# roller-shutter.net
KiCad netlist of a schematic drawn in EAGLE
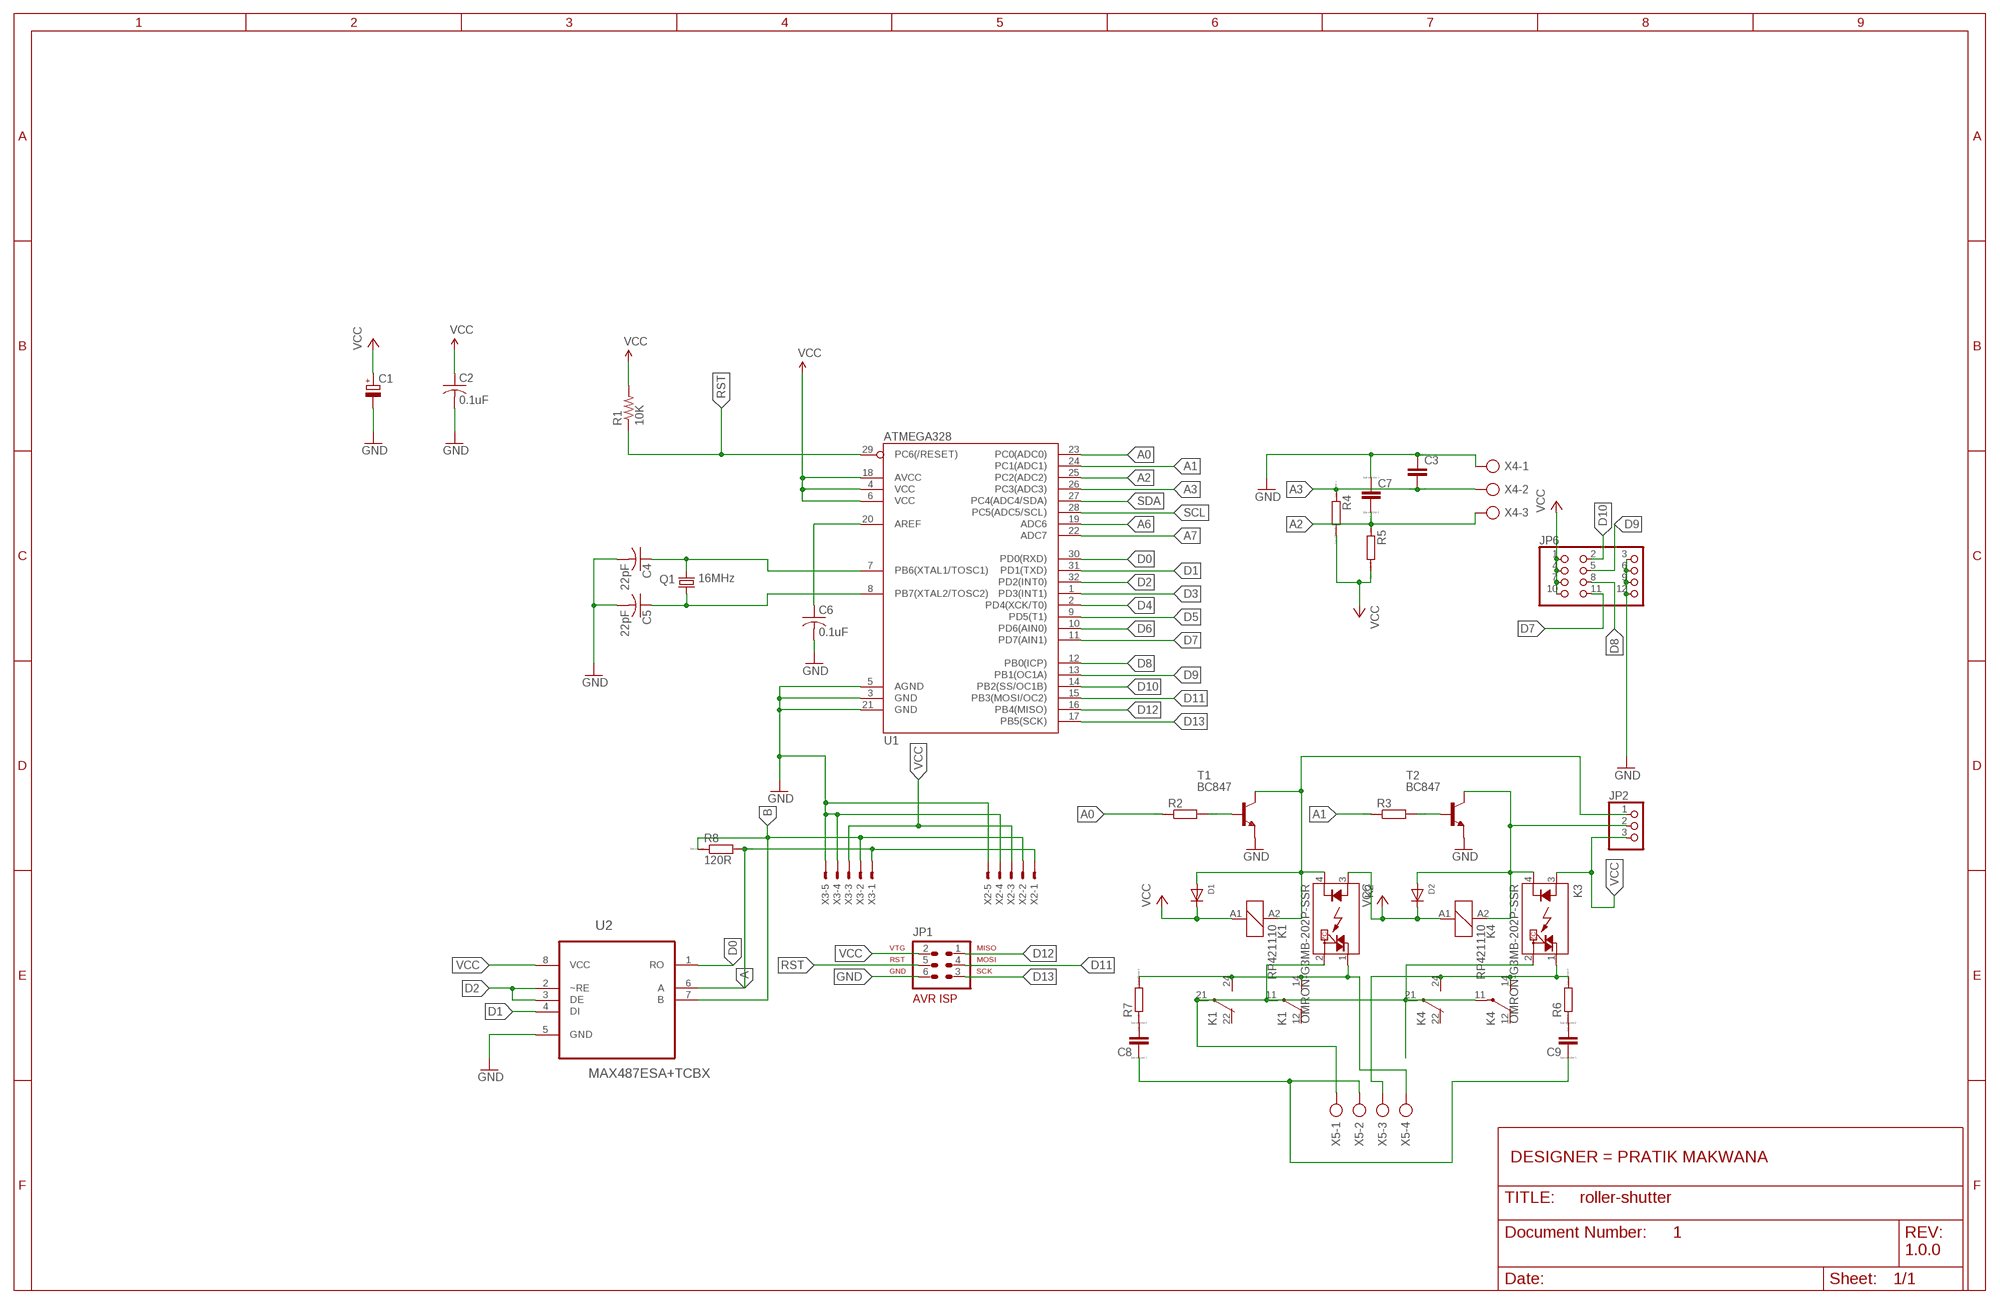
[diagram p0: schematic, sheet 1]

(export (version "E")
  (design (tool "Eeschema 10.0.6"))
  (components
    (comp (ref "C1")
      (value "CPOL-EUSANYO_SMD_C6")
      (footprint "eagle-import:SANYO-OSCON_SMD_C6")
      (libsource (lib "eagle-import") (part "CPOL-EUSANYO_SMD_C6"))
    )
    (comp (ref "C2")
      (value "0.1uF")
      (footprint "eagle-import:C0805")
      (libsource (lib "eagle-import") (part "C-USC0805"))
    )
    (comp (ref "C3") (value "C") (footprint "eagle-import:C0805") (libsource (lib "eagle-import") (part "C")))
    (comp (ref "C4")
      (value "22pF")
      (footprint "eagle-import:C1206")
      (libsource (lib "eagle-import") (part "C-USC1206"))
    )
    (comp (ref "C5")
      (value "22pF")
      (footprint "eagle-import:C1206")
      (libsource (lib "eagle-import") (part "C-USC1206"))
    )
    (comp (ref "C6")
      (value "0.1uF")
      (footprint "eagle-import:C0805")
      (libsource (lib "eagle-import") (part "C-USC0805"))
    )
    (comp (ref "C7") (value "C") (footprint "eagle-import:C0805") (libsource (lib "eagle-import") (part "C")))
    (comp (ref "C8")
      (value "CC1812")
      (footprint "eagle-import:C1812")
      (libsource (lib "eagle-import") (part "CC1812"))
    )
    (comp (ref "C9")
      (value "CC1812")
      (footprint "eagle-import:C1812")
      (libsource (lib "eagle-import") (part "CC1812"))
    )
    (comp (ref "D1")
      (value "DIODE_SOD-123FL")
      (footprint "eagle-import:SOD-123FL")
      (libsource (lib "eagle-import") (part "DIODE_SOD-123FL"))
    )
    (comp (ref "D2")
      (value "DIODE_SOD-123FL")
      (footprint "eagle-import:SOD-123FL")
      (libsource (lib "eagle-import") (part "DIODE_SOD-123FL"))
    )
    (comp (ref "JP1")
      (value "AVR-ISP-6")
      (footprint "eagle-import:AVR-ISP-6")
      (libsource (lib "eagle-import") (part "AVR-ISP-6"))
    )
    (comp (ref "JP2")
      (value "PINHD-1X3")
      (footprint "eagle-import:1X03")
      (libsource (lib "eagle-import") (part "PINHD-1X3"))
    )
    (comp (ref "JP6")
      (value "PINHD-3X4")
      (footprint "eagle-import:3X04")
      (libsource (lib "eagle-import") (part "PINHD-3X4"))
    )
    (comp (ref "K1")
      (value "RP421110")
      (footprint "eagle-import:RP420")
      (fields (field (name "MF") "TYCO ELECTRONICS"))
      (libsource (lib "eagle-import") (part "RP42?1110"))
    )
    (comp (ref "K2")
      (value "OMRON-G3MB-202P-SSR")
      (footprint "eagle-import:OMRON-G3MB-202P-SSR")
      (libsource (lib "eagle-import") (part "OMRON-G3MB-202P-SSR"))
    )
    (comp (ref "K3")
      (value "OMRON-G3MB-202P-SSR")
      (footprint "eagle-import:OMRON-G3MB-202P-SSR")
      (libsource (lib "eagle-import") (part "OMRON-G3MB-202P-SSR"))
    )
    (comp (ref "K4")
      (value "RP421110")
      (footprint "eagle-import:RP420")
      (fields (field (name "MF") "TYCO ELECTRONICS"))
      (libsource (lib "eagle-import") (part "RP42?1110"))
    )
    (comp (ref "Q1")
      (value "16MHz")
      (footprint "eagle-import:HC49_S")
      (libsource (lib "eagle-import") (part "CRYTALHC49S"))
    )
    (comp (ref "R1")
      (value "10K")
      (footprint "eagle-import:R1206")
      (libsource (lib "eagle-import") (part "R-US_R1206"))
    )
    (comp (ref "R2")
      (value "RR1206")
      (footprint "eagle-import:R1206")
      (libsource (lib "eagle-import") (part "RR1206"))
    )
    (comp (ref "R3")
      (value "RR1206")
      (footprint "eagle-import:R1206")
      (libsource (lib "eagle-import") (part "RR1206"))
    )
    (comp (ref "R4")
      (value "RR1206")
      (footprint "eagle-import:R1206")
      (libsource (lib "eagle-import") (part "RR1206"))
    )
    (comp (ref "R5")
      (value "RR1206")
      (footprint "eagle-import:R1206")
      (libsource (lib "eagle-import") (part "RR1206"))
    )
    (comp (ref "R6")
      (value "RR2512")
      (footprint "eagle-import:R2512")
      (libsource (lib "eagle-import") (part "RR2512"))
    )
    (comp (ref "R7")
      (value "RR2512")
      (footprint "eagle-import:R2512")
      (libsource (lib "eagle-import") (part "RR2512"))
    )
    (comp (ref "R8")
      (value "120R")
      (footprint "eagle-import:R0603")
      (libsource (lib "eagle-import") (part "RR0603"))
    )
    (comp (ref "T1")
      (value "BC847")
      (footprint "eagle-import:SOT23")
      (libsource (lib "eagle-import") (part "BC847"))
    )
    (comp (ref "T2")
      (value "BC847")
      (footprint "eagle-import:SOT23")
      (libsource (lib "eagle-import") (part "BC847"))
    )
    (comp (ref "U1")
      (value "ATMEGA328")
      (footprint "eagle-import:TQFP32-08")
      (libsource (lib "eagle-import") (part "ATMEGA328"))
    )
    (comp (ref "U2")
      (value "MAX487ESA+TCBX")
      (footprint "eagle-import:SOIC127P600X175-8N")
      (fields (field (name "MF") "Maxim Integrated"))
      (libsource (lib "eagle-import") (part "MAX487ESA+TCBX"))
    )
    (comp (ref "X2")
      (value "JST-XH-05-PIN-LONG-PAD")
      (footprint "eagle-import:JST-XH-05-PACKAGE-LONG-PAD")
      (libsource (lib "eagle-import") (part "JST-XH-05-PIN-LONG-PAD"))
    )
    (comp (ref "X3")
      (value "JST-XH-05-PIN-LONG-PAD")
      (footprint "eagle-import:JST-XH-05-PACKAGE-LONG-PAD")
      (libsource (lib "eagle-import") (part "JST-XH-05-PIN-LONG-PAD"))
    )
    (comp (ref "X4")
      (value "AK500/3")
      (footprint "eagle-import:AK500_3")
      (libsource (lib "eagle-import") (part "AK500/3"))
    )
    (comp (ref "X5")
      (value "AK500/4")
      (footprint "eagle-import:AK500_4")
      (libsource (lib "eagle-import") (part "AK500/4"))
    )
  )
  (nets
    (net (code "1") (name "A") (class "Default")
      (node (ref "R8") (pin "2") (pinfunction "2_2") (pintype "passive"))
      (node (ref "U2") (pin "6") (pinfunction "A_6") (pintype "bidirectional"))
      (node (ref "X2") (pin "1") (pinfunction "S_1") (pintype "passive"))
      (node (ref "X3") (pin "1") (pinfunction "S_1") (pintype "passive"))
    )
    (net (code "2") (name "A0") (class "Default")
      (node (ref "R2") (pin "1") (pinfunction "1_1") (pintype "passive"))
      (node (ref "U1") (pin "23") (pinfunction "PC0(ADC0)_23") (pintype "bidirectional"))
    )
    (net (code "3") (name "A1") (class "Default")
      (node (ref "R3") (pin "1") (pinfunction "1_1") (pintype "passive"))
      (node (ref "U1") (pin "24") (pinfunction "PC1(ADC1)_24") (pintype "bidirectional"))
    )
    (net (code "4") (name "A2") (class "Default")
      (node (ref "C7") (pin "2") (pinfunction "2_2") (pintype "passive"))
      (node (ref "R5") (pin "1") (pinfunction "1_1") (pintype "passive"))
      (node (ref "U1") (pin "25") (pinfunction "PC2(ADC2)_25") (pintype "bidirectional"))
      (node (ref "X4") (pin "3") (pinfunction "KL_3") (pintype "passive"))
    )
    (net (code "5") (name "A3") (class "Default")
      (node (ref "C3") (pin "2") (pinfunction "2_2") (pintype "passive"))
      (node (ref "R4") (pin "1") (pinfunction "1_1") (pintype "passive"))
      (node (ref "U1") (pin "26") (pinfunction "PC3(ADC3)_26") (pintype "bidirectional"))
      (node (ref "X4") (pin "2") (pinfunction "KL_2") (pintype "passive"))
    )
    (net (code "6") (name "A6") (class "Default")
      (node (ref "U1") (pin "19") (pinfunction "ADC6_19") (pintype "bidirectional"))
    )
    (net (code "7") (name "A7") (class "Default")
      (node (ref "U1") (pin "22") (pinfunction "ADC7_22") (pintype "bidirectional"))
    )
    (net (code "8") (name "B") (class "Default")
      (node (ref "R8") (pin "1") (pinfunction "1_1") (pintype "passive"))
      (node (ref "U2") (pin "7") (pinfunction "B_7") (pintype "bidirectional"))
      (node (ref "X2") (pin "2") (pinfunction "S_2") (pintype "passive"))
      (node (ref "X3") (pin "2") (pinfunction "S_2") (pintype "passive"))
    )
    (net (code "9") (name "D0") (class "Default")
      (node (ref "U1") (pin "30") (pinfunction "PD0(RXD)_30") (pintype "bidirectional"))
      (node (ref "U2") (pin "1") (pinfunction "RO_1") (pintype "output"))
    )
    (net (code "10") (name "D1") (class "Default")
      (node (ref "U1") (pin "31") (pinfunction "PD1(TXD)_31") (pintype "bidirectional"))
      (node (ref "U2") (pin "4") (pinfunction "DI_4") (pintype "input"))
    )
    (net (code "11") (name "D2") (class "Default")
      (node (ref "U1") (pin "32") (pinfunction "PD2(INT0)_32") (pintype "bidirectional"))
      (node (ref "U2") (pin "2") (pinfunction "~{RE}_2") (pintype "input"))
      (node (ref "U2") (pin "3") (pinfunction "DE_3") (pintype "input"))
    )
    (net (code "12") (name "D3") (class "Default")
      (node (ref "U1") (pin "1") (pinfunction "PD3(INT1)_1") (pintype "bidirectional"))
    )
    (net (code "13") (name "D4") (class "Default")
      (node (ref "U1") (pin "2") (pinfunction "PD4(XCK/T0)_2") (pintype "bidirectional"))
    )
    (net (code "14") (name "D5") (class "Default")
      (node (ref "U1") (pin "9") (pinfunction "PD5(T1)_9") (pintype "bidirectional"))
    )
    (net (code "15") (name "D6") (class "Default")
      (node (ref "U1") (pin "10") (pinfunction "PD6(AIN0)_10") (pintype "bidirectional"))
    )
    (net (code "16") (name "D7") (class "Default")
      (node (ref "JP6") (pin "11") (pinfunction "11_11") (pintype "passive"))
      (node (ref "U1") (pin "11") (pinfunction "PD7(AIN1)_11") (pintype "bidirectional"))
    )
    (net (code "17") (name "D8") (class "Default")
      (node (ref "JP6") (pin "8") (pinfunction "8_8") (pintype "passive"))
      (node (ref "U1") (pin "12") (pinfunction "PB0(ICP)_12") (pintype "bidirectional"))
    )
    (net (code "18") (name "D9") (class "Default")
      (node (ref "JP6") (pin "5") (pinfunction "5_5") (pintype "passive"))
      (node (ref "U1") (pin "13") (pinfunction "PB1(OC1A)_13") (pintype "bidirectional"))
    )
    (net (code "19") (name "D10") (class "Default")
      (node (ref "JP6") (pin "2") (pinfunction "2_2") (pintype "passive"))
      (node (ref "U1") (pin "14") (pinfunction "PB2(SS/OC1B)_14") (pintype "bidirectional"))
    )
    (net (code "20") (name "D11") (class "Default")
      (node (ref "JP1") (pin "4") (pinfunction "4_4") (pintype "passive"))
      (node (ref "U1") (pin "15") (pinfunction "PB3(MOSI/OC2)_15") (pintype "bidirectional"))
    )
    (net (code "21") (name "D12") (class "Default")
      (node (ref "JP1") (pin "1") (pinfunction "1_1") (pintype "passive"))
      (node (ref "U1") (pin "16") (pinfunction "PB4(MISO)_16") (pintype "bidirectional"))
    )
    (net (code "22") (name "D13") (class "Default")
      (node (ref "JP1") (pin "3") (pinfunction "3_3") (pintype "passive"))
      (node (ref "U1") (pin "17") (pinfunction "PB5(SCK)_17") (pintype "bidirectional"))
    )
    (net (code "23") (name "GND") (class "Default")
      (node (ref "C1") (pin "-") (pinfunction "-_-") (pintype "passive"))
      (node (ref "C2") (pin "2") (pinfunction "2_2") (pintype "passive"))
      (node (ref "C3") (pin "1") (pinfunction "1_1") (pintype "passive"))
      (node (ref "C4") (pin "2") (pinfunction "2_2") (pintype "passive"))
      (node (ref "C5") (pin "2") (pinfunction "2_2") (pintype "passive"))
      (node (ref "C6") (pin "2") (pinfunction "2_2") (pintype "passive"))
      (node (ref "C7") (pin "1") (pinfunction "1_1") (pintype "passive"))
      (node (ref "JP1") (pin "6") (pinfunction "6_6") (pintype "passive"))
      (node (ref "JP6") (pin "12") (pinfunction "12_12") (pintype "passive"))
      (node (ref "JP6") (pin "3") (pinfunction "3_3") (pintype "passive"))
      (node (ref "JP6") (pin "6") (pinfunction "6_6") (pintype "passive"))
      (node (ref "JP6") (pin "9") (pinfunction "9_9") (pintype "passive"))
      (node (ref "T1") (pin "2") (pinfunction "E_2") (pintype "passive"))
      (node (ref "T2") (pin "2") (pinfunction "E_2") (pintype "passive"))
      (node (ref "U1") (pin "21") (pinfunction "GND_21") (pintype "bidirectional"))
      (node (ref "U1") (pin "3") (pinfunction "GND_3") (pintype "bidirectional"))
      (node (ref "U1") (pin "5") (pinfunction "AGND_5") (pintype "bidirectional"))
      (node (ref "U2") (pin "5") (pinfunction "GND_5") (pintype "passive"))
      (node (ref "X2") (pin "4") (pinfunction "S_4") (pintype "passive"))
      (node (ref "X2") (pin "5") (pinfunction "S_5") (pintype "passive"))
      (node (ref "X3") (pin "4") (pinfunction "S_4") (pintype "passive"))
      (node (ref "X3") (pin "5") (pinfunction "S_5") (pintype "passive"))
      (node (ref "X4") (pin "1") (pinfunction "KL_1") (pintype "passive"))
    )
    (net (code "24") (name "Net-(C8-Pad2)") (class "Default")
      (node (ref "C8") (pin "2") (pinfunction "2_2") (pintype "passive"))
      (node (ref "R7") (pin "1") (pinfunction "1_1") (pintype "passive"))
    )
    (net (code "25") (name "Net-(C9-Pad2)") (class "Default")
      (node (ref "C9") (pin "2") (pinfunction "2_2") (pintype "passive"))
      (node (ref "R6") (pin "1") (pinfunction "1_1") (pintype "passive"))
    )
    (net (code "26") (name "Net-(K1A-1)") (class "Default")
      (node (ref "D1") (pin "A") (pinfunction "A_A") (pintype "passive"))
      (node (ref "JP2") (pin "1") (pinfunction "1_1") (pintype "passive"))
      (node (ref "K1") (pin "A2") (pinfunction "1_A2") (pintype "passive"))
      (node (ref "K2") (pin "4") (pinfunction "K_4") (pintype "passive"))
      (node (ref "T1") (pin "3") (pinfunction "C_3") (pintype "passive"))
    )
    (net (code "27") (name "Net-(K1B-P)") (class "Default")
      (node (ref "K1") (pin "11") (pinfunction "P_11") (pintype "passive"))
      (node (ref "K1") (pin "21") (pinfunction "P_21") (pintype "passive"))
      (node (ref "K2") (pin "2") (pinfunction "DS2_2") (pintype "passive"))
      (node (ref "K3") (pin "2") (pinfunction "DS2_2") (pintype "passive"))
      (node (ref "K4") (pin "11") (pinfunction "P_11") (pintype "passive"))
      (node (ref "K4") (pin "21") (pinfunction "P_21") (pintype "passive"))
      (node (ref "X5") (pin "1") (pinfunction "KL_1") (pintype "passive"))
    )
    (net (code "28") (name "Net-(K1B-S)") (class "Default")
      (node (ref "K1") (pin "14") (pinfunction "S_14") (pintype "passive"))
      (node (ref "K1") (pin "24") (pinfunction "S_24") (pintype "passive"))
      (node (ref "K2") (pin "1") (pinfunction "DS1_1") (pintype "passive"))
      (node (ref "R7") (pin "2") (pinfunction "2_2") (pintype "passive"))
      (node (ref "X5") (pin "4") (pinfunction "KL_4") (pintype "passive"))
    )
    (net (code "29") (name "Net-(K3-DS1)") (class "Default")
      (node (ref "K3") (pin "1") (pinfunction "DS1_1") (pintype "passive"))
      (node (ref "K4") (pin "14") (pinfunction "S_14") (pintype "passive"))
      (node (ref "K4") (pin "24") (pinfunction "S_24") (pintype "passive"))
      (node (ref "R6") (pin "2") (pinfunction "2_2") (pintype "passive"))
      (node (ref "X5") (pin "3") (pinfunction "KL_3") (pintype "passive"))
    )
    (net (code "30") (name "Net-(K3-K)") (class "Default")
      (node (ref "D2") (pin "A") (pinfunction "A_A") (pintype "passive"))
      (node (ref "JP2") (pin "2") (pinfunction "2_2") (pintype "passive"))
      (node (ref "K3") (pin "4") (pinfunction "K_4") (pintype "passive"))
      (node (ref "K4") (pin "A2") (pinfunction "1_A2") (pintype "passive"))
      (node (ref "T2") (pin "3") (pinfunction "C_3") (pintype "passive"))
    )
    (net (code "31") (name "Net-(T1-B)") (class "Default")
      (node (ref "R2") (pin "2") (pinfunction "2_2") (pintype "passive"))
      (node (ref "T1") (pin "1") (pinfunction "B_1") (pintype "passive"))
    )
    (net (code "32") (name "Net-(T2-B)") (class "Default")
      (node (ref "R3") (pin "2") (pinfunction "2_2") (pintype "passive"))
      (node (ref "T2") (pin "1") (pinfunction "B_1") (pintype "passive"))
    )
    (net (code "33") (name "Net-(U1-AREF)") (class "Default")
      (node (ref "C6") (pin "1") (pinfunction "1_1") (pintype "passive"))
      (node (ref "U1") (pin "20") (pinfunction "AREF_20") (pintype "bidirectional"))
    )
    (net (code "34") (name "Net-(U1-PB6(XTAL1{slash}TOSC1))") (class "Default")
      (node (ref "C4") (pin "1") (pinfunction "1_1") (pintype "passive"))
      (node (ref "Q1") (pin "2") (pinfunction "2_2") (pintype "passive"))
      (node (ref "U1") (pin "7") (pinfunction "PB6(XTAL1/TOSC1)_7") (pintype "bidirectional"))
    )
    (net (code "35") (name "Net-(U1-PB7(XTAL2{slash}TOSC2))") (class "Default")
      (node (ref "C5") (pin "1") (pinfunction "1_1") (pintype "passive"))
      (node (ref "Q1") (pin "1") (pinfunction "1_1") (pintype "passive"))
      (node (ref "U1") (pin "8") (pinfunction "PB7(XTAL2/TOSC2)_8") (pintype "bidirectional"))
    )
    (net (code "36") (name "Net-(X5B-KL)") (class "Default")
      (node (ref "C8") (pin "1") (pinfunction "1_1") (pintype "passive"))
      (node (ref "C9") (pin "1") (pinfunction "1_1") (pintype "passive"))
      (node (ref "X5") (pin "2") (pinfunction "KL_2") (pintype "passive"))
    )
    (net (code "37") (name "RST") (class "Default")
      (node (ref "JP1") (pin "5") (pinfunction "5_5") (pintype "passive"))
      (node (ref "R1") (pin "1") (pinfunction "1_1") (pintype "passive"))
      (node (ref "U1") (pin "29") (pinfunction "PC6(/RESET)_29") (pintype "bidirectional"))
    )
    (net (code "38") (name "SCL") (class "Default")
      (node (ref "U1") (pin "28") (pinfunction "PC5(ADC5/SCL)_28") (pintype "bidirectional"))
    )
    (net (code "39") (name "SDA") (class "Default")
      (node (ref "U1") (pin "27") (pinfunction "PC4(ADC4/SDA)_27") (pintype "bidirectional"))
    )
    (net (code "40") (name "VCC") (class "Default")
      (node (ref "C1") (pin "+") (pinfunction "+_+") (pintype "passive"))
      (node (ref "C2") (pin "1") (pinfunction "1_1") (pintype "passive"))
      (node (ref "D1") (pin "C") (pinfunction "C_C") (pintype "passive"))
      (node (ref "D2") (pin "C") (pinfunction "C_C") (pintype "passive"))
      (node (ref "JP1") (pin "2") (pinfunction "2_2") (pintype "passive"))
      (node (ref "JP2") (pin "3") (pinfunction "3_3") (pintype "passive"))
      (node (ref "JP6") (pin "1") (pinfunction "1_1") (pintype "passive"))
      (node (ref "JP6") (pin "10") (pinfunction "10_10") (pintype "passive"))
      (node (ref "JP6") (pin "4") (pinfunction "4_4") (pintype "passive"))
      (node (ref "JP6") (pin "7") (pinfunction "7_7") (pintype "passive"))
      (node (ref "K1") (pin "A1") (pinfunction "2_A1") (pintype "passive"))
      (node (ref "K2") (pin "3") (pinfunction "A_3") (pintype "passive"))
      (node (ref "K3") (pin "3") (pinfunction "A_3") (pintype "passive"))
      (node (ref "K4") (pin "A1") (pinfunction "2_A1") (pintype "passive"))
      (node (ref "R1") (pin "2") (pinfunction "2_2") (pintype "passive"))
      (node (ref "R4") (pin "2") (pinfunction "2_2") (pintype "passive"))
      (node (ref "R5") (pin "2") (pinfunction "2_2") (pintype "passive"))
      (node (ref "U1") (pin "18") (pinfunction "AVCC_18") (pintype "bidirectional"))
      (node (ref "U1") (pin "4") (pinfunction "VCC_4") (pintype "bidirectional"))
      (node (ref "U1") (pin "6") (pinfunction "VCC_6") (pintype "bidirectional"))
      (node (ref "U2") (pin "8") (pinfunction "VCC_8") (pintype "power_in"))
      (node (ref "X2") (pin "3") (pinfunction "S_3") (pintype "passive"))
      (node (ref "X3") (pin "3") (pinfunction "S_3") (pintype "passive"))
    )
    (net (code "41") (name "unconnected-(K1B-O-Pad12)") (class "Default")
      (node (ref "K1") (pin "12") (pinfunction "O_12") (pintype "passive"))
    )
    (net (code "42") (name "unconnected-(K1C-O-Pad22)") (class "Default")
      (node (ref "K1") (pin "22") (pinfunction "O_22") (pintype "passive"))
    )
    (net (code "43") (name "unconnected-(K4B-O-Pad12)") (class "Default")
      (node (ref "K4") (pin "12") (pinfunction "O_12") (pintype "passive"))
    )
    (net (code "44") (name "unconnected-(K4C-O-Pad22)") (class "Default")
      (node (ref "K4") (pin "22") (pinfunction "O_22") (pintype "passive"))
    )
  )
)
